# Schematic.net
KiCad netlist of a schematic drawn in Altium Designer
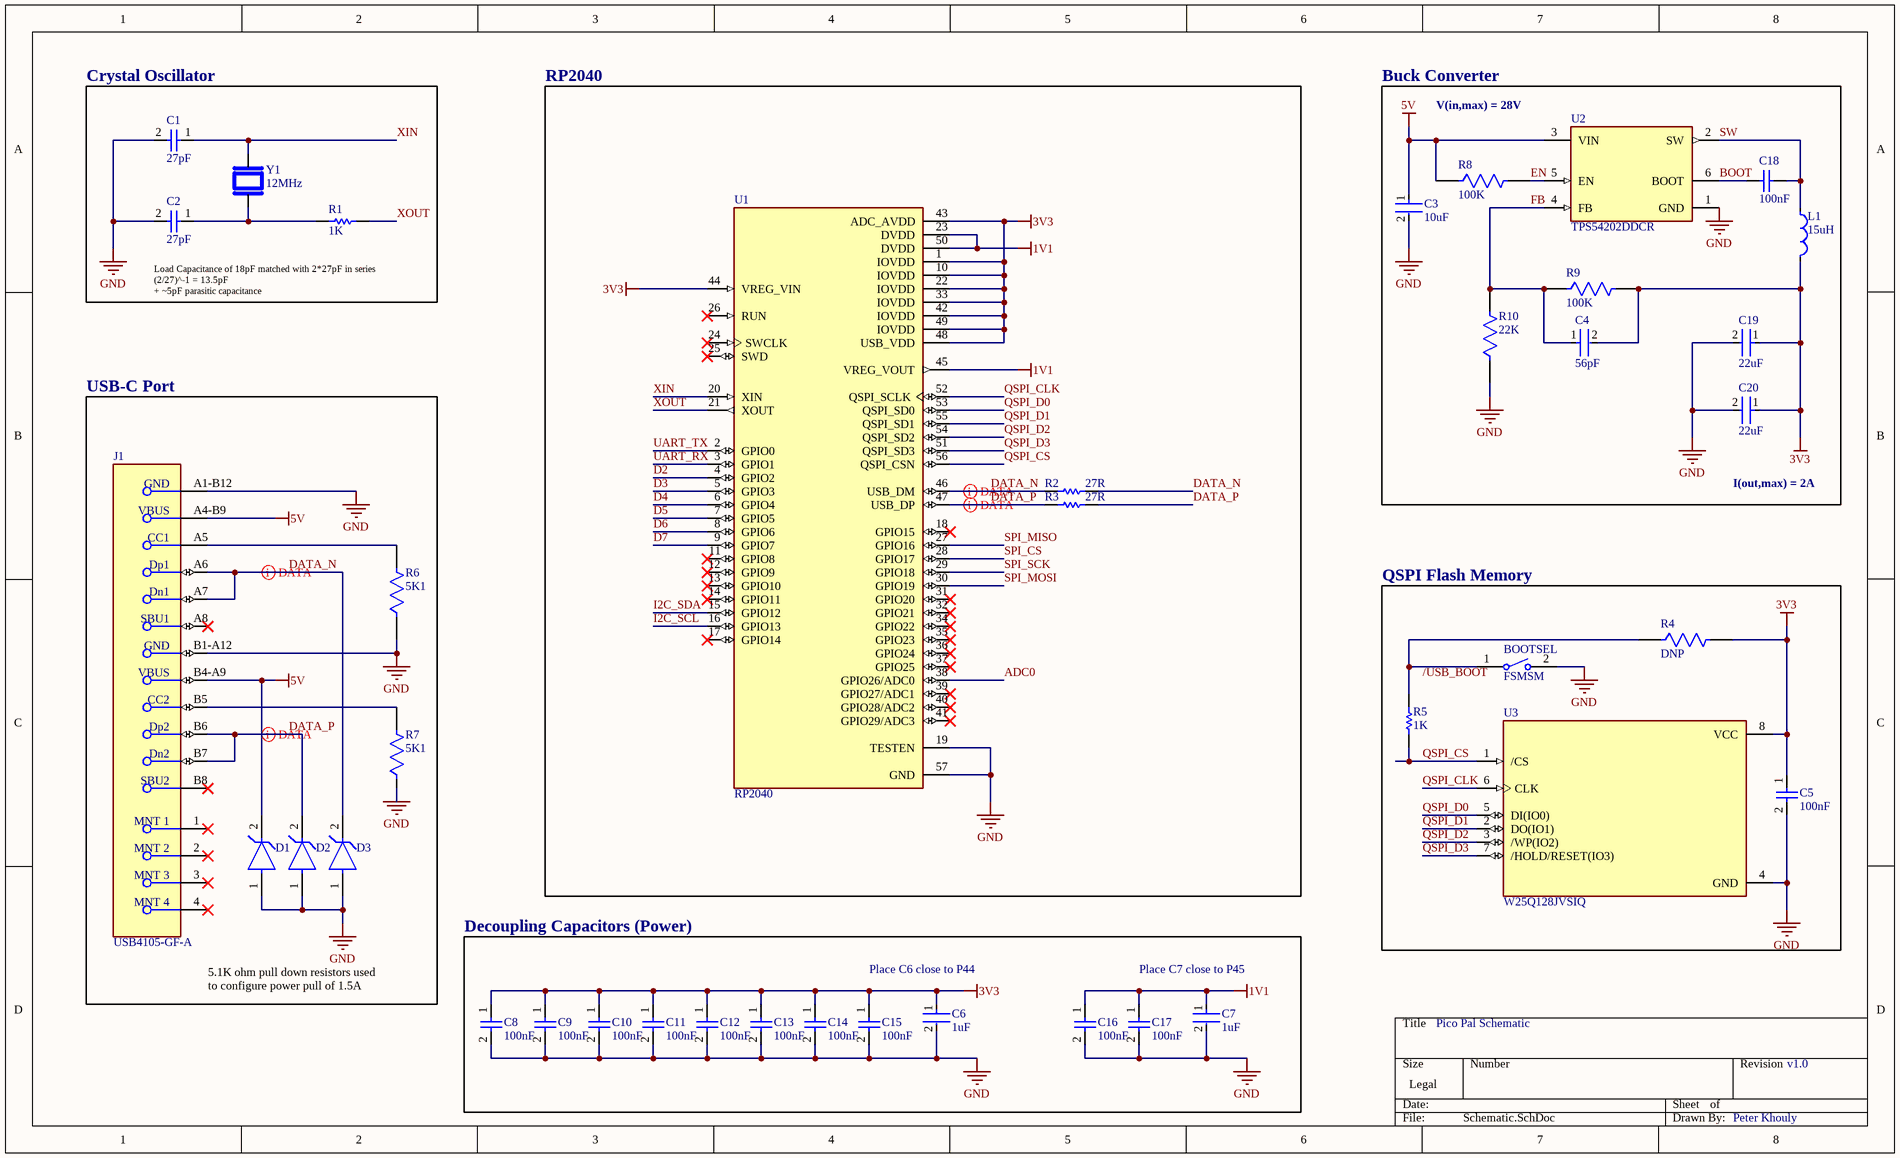
[diagram p0: Schematic.SchDoc]

(export (version "E")
  (design (tool "Eeschema 10.0.6"))
  (components
    (comp (ref "BOOTSEL")
      (value "FSMSM")
      (footprint "TECO-FSMSM-2_V")
      (description "FSMSM Push Button Switch, 50 mA, -35 to 85 degC, 2-Pin SMD, RoHS, Bulk")
      (fields (field (name "MANUFACTURER") "TE Connectivity"))
      (libsource (lib "Altium Content Vault") (part "SW-SPST-2_C"))
    )
    (comp (ref "C1")
      (value "27pF")
      (footprint "CAPC1005X55X25LL05T10")
      (fields (field (name "PART NUMBER") "GRM1555C1H270JA01D") (field (name "MANUFACTURER") "Murata"))
      (libsource (lib "Altium Content Vault") (part "CAP"))
    )
    (comp (ref "C2")
      (value "27pF")
      (footprint "CAPC1005X55X25LL05T10")
      (fields (field (name "PART NUMBER") "GRM1555C1H270JA01D") (field (name "MANUFACTURER") "Murata"))
      (libsource (lib "Altium Content Vault") (part "CAP"))
    )
    (comp (ref "C3")
      (value "10uF")
      (footprint "FP-GRM15-0_2-MFG")
      (description "CAP CER 10UF 6.3V X6S 0402")
      (fields (field (name "TOLERANCE") "20%") (field (name "MANUFACTURER PART NUMBER") "GRM155C80J106ME11D"))
      (libsource (lib "Altium Content Vault") (part "b4654b650e69147ec39a6b967a45e02"))
    )
    (comp (ref "C4")
      (value "56pF")
      (footprint "FP-0402-L_1_0_1-W_0_5_0_1-MFG")
      (description "General Purpose Ceramic Capacitor, 0402, 56pF, 5%, C0G, 30ppm/°C, 50V")
      (fields (field (name "TOLERANCE") "5%") (field (name "VOLTAGE") "50V"))
      (libsource (lib "Altium Content Vault") (part "b4654b650e69147ec39a6b967a45e02"))
    )
    (comp (ref "C5")
      (value "100nF")
      (footprint "CAPC1005X56X25LL10T15")
      (fields
        (field (name "MANUFACTURER") "AVX Interconnect / Elco")
        (field (name "PART NUMBER") "04026D104KAT2A")
      )
      (libsource (lib "Altium Content Vault") (part "CAP"))
    )
    (comp (ref "C6")
      (value "1uF")
      (footprint "FP-GRM15-0_1-MFG")
      (description "CAP CER 1UF 10V X5R 0402")
      (fields
        (field (name "OCTOPART") "https://octopart.com/grm155r61a105ke15d-murata-197442")
        (field (name "MANUFACTURER PART NUMBER") "GRM155R61A105KE15D")
      )
      (libsource (lib "Altium Content Vault") (part "02cd4be3c70576c341d710602a673aa"))
    )
    (comp (ref "C7")
      (value "1uF")
      (footprint "FP-GRM15-0_1-MFG")
      (description "CAP CER 1UF 10V X5R 0402")
      (fields
        (field (name "OCTOPART") "https://octopart.com/grm155r61a105ke15d-murata-197442")
        (field (name "MANUFACTURER PART NUMBER") "GRM155R61A105KE15D")
      )
      (libsource (lib "Altium Content Vault") (part "02cd4be3c70576c341d710602a673aa"))
    )
    (comp (ref "C8")
      (value "100nF")
      (footprint "CAPC1005X56X25LL10T15")
      (fields
        (field (name "MANUFACTURER") "AVX Interconnect / Elco")
        (field (name "PART NUMBER") "04026D104KAT2A")
      )
      (libsource (lib "Altium Content Vault") (part "CAP"))
    )
    (comp (ref "C9")
      (value "100nF")
      (footprint "CAPC1005X56X25LL10T15")
      (fields
        (field (name "MANUFACTURER") "AVX Interconnect / Elco")
        (field (name "PART NUMBER") "04026D104KAT2A")
      )
      (libsource (lib "Altium Content Vault") (part "CAP"))
    )
    (comp (ref "C10")
      (value "100nF")
      (footprint "CAPC1005X56X25LL10T15")
      (fields
        (field (name "MANUFACTURER") "AVX Interconnect / Elco")
        (field (name "PART NUMBER") "04026D104KAT2A")
      )
      (libsource (lib "Altium Content Vault") (part "CAP"))
    )
    (comp (ref "C11")
      (value "100nF")
      (footprint "CAPC1005X56X25LL10T15")
      (fields
        (field (name "MANUFACTURER") "AVX Interconnect / Elco")
        (field (name "PART NUMBER") "04026D104KAT2A")
      )
      (libsource (lib "Altium Content Vault") (part "CAP"))
    )
    (comp (ref "C12")
      (value "100nF")
      (footprint "CAPC1005X56X25LL10T15")
      (fields
        (field (name "MANUFACTURER") "AVX Interconnect / Elco")
        (field (name "PART NUMBER") "04026D104KAT2A")
      )
      (libsource (lib "Altium Content Vault") (part "CAP"))
    )
    (comp (ref "C13")
      (value "100nF")
      (footprint "CAPC1005X56X25LL10T15")
      (fields
        (field (name "MANUFACTURER") "AVX Interconnect / Elco")
        (field (name "PART NUMBER") "04026D104KAT2A")
      )
      (libsource (lib "Altium Content Vault") (part "CAP"))
    )
    (comp (ref "C14")
      (value "100nF")
      (footprint "CAPC1005X56X25LL10T15")
      (fields
        (field (name "MANUFACTURER") "AVX Interconnect / Elco")
        (field (name "PART NUMBER") "04026D104KAT2A")
      )
      (libsource (lib "Altium Content Vault") (part "CAP"))
    )
    (comp (ref "C15")
      (value "100nF")
      (footprint "CAPC1005X56X25LL10T15")
      (fields
        (field (name "MANUFACTURER") "AVX Interconnect / Elco")
        (field (name "PART NUMBER") "04026D104KAT2A")
      )
      (libsource (lib "Altium Content Vault") (part "CAP"))
    )
    (comp (ref "C16")
      (value "100nF")
      (footprint "CAPC1005X56X25LL10T15")
      (fields
        (field (name "MANUFACTURER") "AVX Interconnect / Elco")
        (field (name "PART NUMBER") "04026D104KAT2A")
      )
      (libsource (lib "Altium Content Vault") (part "CAP"))
    )
    (comp (ref "C17")
      (value "100nF")
      (footprint "CAPC1005X56X25LL10T15")
      (fields
        (field (name "MANUFACTURER") "AVX Interconnect / Elco")
        (field (name "PART NUMBER") "04026D104KAT2A")
      )
      (libsource (lib "Altium Content Vault") (part "CAP"))
    )
    (comp (ref "C18")
      (value "100nF")
      (footprint "CAPC1005X56X25LL10T15")
      (fields
        (field (name "MANUFACTURER") "AVX Interconnect / Elco")
        (field (name "PART NUMBER") "04026D104KAT2A")
      )
      (libsource (lib "") (part "CAP_1"))
    )
    (comp (ref "C19")
      (value "22uF")
      (footprint "FP-CL746-IPC_C")
      (description "Cap Ceramic 22uF 6.3V X5R ±20% SMD 0402 +85°C Paper T/R")
      (fields (field (name "TOLERANCE") "20%"))
      (libsource (lib "Altium Content Vault") (part "b4654b650e69147ec39a6b967a45e02"))
    )
    (comp (ref "C20")
      (value "22uF")
      (footprint "FP-CL746-IPC_C")
      (description "Cap Ceramic 22uF 6.3V X5R ±20% SMD 0402 +85°C Paper T/R")
      (fields (field (name "TOLERANCE") "20%"))
      (libsource (lib "Altium Content Vault") (part "b4654b650e69147ec39a6b967a45e02"))
    )
    (comp (ref "D1")
      (value "~")
      (footprint "FP-SLP1006P2-MFG")
      (description "TVS DIODE 33VWM 60VC SLP1006P2")
      (libsource (lib "Altium Content Vault") (part "3fba79ac723ca0a4e69928609483429"))
    )
    (comp (ref "D2")
      (value "~")
      (footprint "FP-SLP1006P2-MFG")
      (description "TVS DIODE 33VWM 60VC SLP1006P2")
      (libsource (lib "Altium Content Vault") (part "3fba79ac723ca0a4e69928609483429"))
    )
    (comp (ref "D3")
      (value "~")
      (footprint "FP-SLP1006P2-MFG")
      (description "TVS DIODE 33VWM 60VC SLP1006P2")
      (libsource (lib "Altium Content Vault") (part "3fba79ac723ca0a4e69928609483429"))
    )
    (comp (ref "J1")
      (value "USB4105-GF-A")
      (footprint "FP-USB4105-GF-A-MFG")
      (description "CONN RCPT USB2.0 TYPEC 5A")
      (fields
        (field (name "MANUFACTURER") "GCT")
        (field (name "OCTOPART") "https://octopart.com/usb4105-gf-a-gct-106627878")
      )
      (libsource (lib "Altium Content Vault") (part "e7c17a616881a82b79941196b4bec10"))
    )
    (comp (ref "L1")
      (value "15uH")
      (footprint "FP-MLZ2012-1_25-IPC_B")
      (description "Shielded Multilayer Inductor 15uH ±20% 350mA 611mΩ SMD 0805")
      (fields (field (name "TOLERANCE") "20%"))
      (libsource (lib "Altium Content Vault") (part "725321dda6339637d4d059423bc1c3c"))
    )
    (comp (ref "R1")
      (value "1K")
      (footprint "RESC1005X40X25NL05T05")
      (description "Chip Resistor, 1 KOhm, +/- 1%, 100 mW, -55 to 155 degC, 0402 (1005 Metric), RoHS, Tape and Reel")
      (fields (field (name "PARTNUMBER") "ERJ-2RKF1001X") (field (name "MANUFACTURER") "Basic Passives"))
      (libsource (lib "Altium Content Vault") (part "RES-2"))
    )
    (comp (ref "R2")
      (value "27R")
      (footprint "RESC1005X40X25LL05T05")
      (fields (field (name "MANUFACTURER") "Panasonic") (field (name "PART NUMBER") "ERJ-2GEJ270X"))
      (libsource (lib "Altium Content Vault") (part "RES"))
    )
    (comp (ref "R3")
      (value "27R")
      (footprint "RESC1005X40X25LL05T05")
      (fields (field (name "MANUFACTURER") "Panasonic") (field (name "PART NUMBER") "ERJ-2GEJ270X"))
      (libsource (lib "Altium Content Vault") (part "RES"))
    )
    (comp (ref "R4")
      (value "DNP")
      (footprint "FP-CRCW1206-e3-IPC_C")
      (description "RES Thick Film, 10kΩ, 1%, 0.25W, 100ppm/°C, 1206")
      (fields (field (name "TOLERANCE") "1%"))
      (libsource (lib "Altium Content Vault") (part "1029c3af85768c4190bb7ad29bc67b5"))
    )
    (comp (ref "R5")
      (value "1K")
      (footprint "RESC1005X40X25NL05T05")
      (description "Chip Resistor, 1 KOhm, +/- 1%, 100 mW, -55 to 155 degC, 0402 (1005 Metric), RoHS, Tape and Reel")
      (fields (field (name "PARTNUMBER") "ERJ-2RKF1001X") (field (name "MANUFACTURER") "Basic Passives"))
      (libsource (lib "Altium Content Vault") (part "RES-2"))
    )
    (comp (ref "R6")
      (value "5K1")
      (footprint "FP-ERJ2RK-IPC_A")
      (description "RES SMD 5.1K OHM 1% 1/10W 0402")
      (fields (field (name "TOLERANCE") "1%"))
      (libsource (lib "Altium Content Vault") (part "1029c3af85768c4190bb7ad29bc67b5"))
    )
    (comp (ref "R7")
      (value "5K1")
      (footprint "FP-ERJ2RK-IPC_A")
      (description "RES SMD 5.1K OHM 1% 1/10W 0402")
      (fields (field (name "TOLERANCE") "1%"))
      (libsource (lib "Altium Content Vault") (part "1029c3af85768c4190bb7ad29bc67b5"))
    )
    (comp (ref "R8")
      (value "100K")
      (footprint "FP-ERJ2RK-IPC_C")
      (description "RES SMD 100K OHM 1% 1/10W 0402")
      (fields (field (name "TOLERANCE") "1%"))
      (libsource (lib "Altium Content Vault") (part "1029c3af85768c4190bb7ad29bc67b5"))
    )
    (comp (ref "R9")
      (value "100K")
      (footprint "FP-ERJ2RK-IPC_C")
      (description "RES SMD 100K OHM 1% 1/10W 0402")
      (fields (field (name "TOLERANCE") "1%"))
      (libsource (lib "Altium Content Vault") (part "1029c3af85768c4190bb7ad29bc67b5"))
    )
    (comp (ref "R10")
      (value "22K")
      (footprint "FP-ERJ2RK-MFG")
      (description "RES SMD 22K OHM 1% 1/10W 0402")
      (fields (field (name "TOLERANCE") "1%"))
      (libsource (lib "Altium Content Vault") (part "1029c3af85768c4190bb7ad29bc67b5"))
    )
    (comp (ref "U1")
      (value "RP2040")
      (footprint "QFN40P700X700X90-57N")
      (description "RP2040 chip for Raspberry Pi Pico - ARMÂ® CortexÂ®-M0+ MCU 32-Bit")
      (fields (field (name "MF") "Raspberry Pi"))
      (libsource (lib "RP2040") (part "RP2040"))
    )
    (comp (ref "U2")
      (value "TPS54202DDCR")
      (footprint "FP-DDC0006A-IPC_B")
      (description "IC REG BUCK ADJ 2A TSOT23-6")
      (libsource (lib "Altium Content Vault") (part "35c2d3f1afc239a386b2ba50eead654"))
    )
    (comp (ref "U3")
      (value "W25Q128JVSIQ")
      (footprint "SOIC127P790X216-8N")
      (description "FLASH - NOR Memory IC 128Mb (16M x 8) SPI - Quad I/O, QPI, DTR 133 MHz 8-SOIC")
      (fields (field (name "MF") "Winbond Electronics"))
      (libsource (lib "W25Q128JVSIQ") (part "W25Q128JVSIQ"))
    )
    (comp (ref "Y1")
      (value "12MHz")
      (footprint "XTAL_ABLS-12.000MHZ-B4-T")
      (description "HC/49US (AT49) SMD LOW PROFILE CRYSTAL")
      (fields (field (name "MF") "Abracon LLC") (field (name "MP") "ABLS-12.000MHZ-B4-T"))
      (libsource (lib "ABLS-12.000MHZ-B4-T") (part "ABLS-12.000MHZ-B4-T"))
    )
  )
  (nets
    (net (code "1") (name "/ADC0") (class "Default")
      (node (ref "U1") (pin "38") (pinfunction "GPIO26/ADC0_38") (pintype "bidirectional"))
    )
    (net (code "2") (name "/BOOT") (class "Default")
      (node (ref "C18") (pin "2") (pinfunction "2_2") (pintype "passive"))
      (node (ref "U2") (pin "6") (pinfunction "BOOT_6") (pintype "passive"))
    )
    (net (code "3") (name "/D2") (class "Default")
      (node (ref "U1") (pin "4") (pinfunction "GPIO2_4") (pintype "bidirectional"))
    )
    (net (code "4") (name "/D3") (class "Default")
      (node (ref "U1") (pin "5") (pinfunction "GPIO3_5") (pintype "bidirectional"))
    )
    (net (code "5") (name "/D4") (class "Default")
      (node (ref "U1") (pin "6") (pinfunction "GPIO4_6") (pintype "bidirectional"))
    )
    (net (code "6") (name "/D5") (class "Default")
      (node (ref "U1") (pin "7") (pinfunction "GPIO5_7") (pintype "bidirectional"))
    )
    (net (code "7") (name "/D6") (class "Default")
      (node (ref "U1") (pin "8") (pinfunction "GPIO6_8") (pintype "bidirectional"))
    )
    (net (code "8") (name "/D7") (class "Default")
      (node (ref "U1") (pin "9") (pinfunction "GPIO7_9") (pintype "bidirectional"))
    )
    (net (code "9") (name "/DATA_N") (class "Default")
      (node (ref "D3") (pin "2") (pinfunction "C_2") (pintype "passive"))
      (node (ref "J1") (pin "A6") (pinfunction "Dp1_A6") (pintype "bidirectional"))
      (node (ref "J1") (pin "A7") (pinfunction "Dn1_A7") (pintype "bidirectional"))
      (node (ref "R2") (pin "1") (pinfunction "1_1") (pintype "passive"))
      (node (ref "R2") (pin "2") (pinfunction "2_2") (pintype "passive"))
      (node (ref "U1") (pin "46") (pinfunction "USB_DM_46") (pintype "bidirectional"))
    )
    (net (code "10") (name "/DATA_P") (class "Default")
      (node (ref "D2") (pin "2") (pinfunction "C_2") (pintype "passive"))
      (node (ref "J1") (pin "B6") (pinfunction "Dp2_B6") (pintype "bidirectional"))
      (node (ref "J1") (pin "B7") (pinfunction "Dn2_B7") (pintype "bidirectional"))
      (node (ref "R3") (pin "1") (pinfunction "1_1") (pintype "passive"))
      (node (ref "R3") (pin "2") (pinfunction "2_2") (pintype "passive"))
      (node (ref "U1") (pin "47") (pinfunction "USB_DP_47") (pintype "bidirectional"))
    )
    (net (code "11") (name "/EN") (class "Default")
      (node (ref "R8") (pin "2") (pinfunction "2_2") (pintype "passive"))
      (node (ref "U2") (pin "5") (pinfunction "EN_5") (pintype "input"))
    )
    (net (code "12") (name "/FB") (class "Default")
      (node (ref "C4") (pin "1") (pinfunction "1_1") (pintype "passive"))
      (node (ref "R10") (pin "2") (pinfunction "2_2") (pintype "passive"))
      (node (ref "R9") (pin "1") (pinfunction "1_1") (pintype "passive"))
      (node (ref "U2") (pin "4") (pinfunction "FB_4") (pintype "input"))
    )
    (net (code "13") (name "/I2C_SCL") (class "Default")
      (node (ref "U1") (pin "16") (pinfunction "GPIO13_16") (pintype "bidirectional"))
    )
    (net (code "14") (name "/I2C_SDA") (class "Default")
      (node (ref "U1") (pin "15") (pinfunction "GPIO12_15") (pintype "bidirectional"))
    )
    (net (code "15") (name "/QSPI_CLK") (class "Default")
      (node (ref "U1") (pin "52") (pinfunction "QSPI_SCLK_52") (pintype "bidirectional"))
      (node (ref "U3") (pin "6") (pinfunction "CLK_6") (pintype "input"))
    )
    (net (code "16") (name "/QSPI_CS") (class "Default")
      (node (ref "R5") (pin "1") (pinfunction "1_1") (pintype "passive"))
      (node (ref "U1") (pin "56") (pinfunction "QSPI_CSN_56") (pintype "bidirectional"))
      (node (ref "U3") (pin "1") (pinfunction "/CS_1") (pintype "input"))
    )
    (net (code "17") (name "/QSPI_D0") (class "Default")
      (node (ref "U1") (pin "53") (pinfunction "QSPI_SD0_53") (pintype "bidirectional"))
      (node (ref "U3") (pin "5") (pinfunction "DI(IO0)_5") (pintype "bidirectional"))
    )
    (net (code "18") (name "/QSPI_D1") (class "Default")
      (node (ref "U1") (pin "55") (pinfunction "QSPI_SD1_55") (pintype "bidirectional"))
      (node (ref "U3") (pin "2") (pinfunction "DO(IO1)_2") (pintype "bidirectional"))
    )
    (net (code "19") (name "/QSPI_D2") (class "Default")
      (node (ref "U1") (pin "54") (pinfunction "QSPI_SD2_54") (pintype "bidirectional"))
      (node (ref "U3") (pin "3") (pinfunction "/WP(IO2)_3") (pintype "bidirectional"))
    )
    (net (code "20") (name "/QSPI_D3") (class "Default")
      (node (ref "U1") (pin "51") (pinfunction "QSPI_SD3_51") (pintype "bidirectional"))
      (node (ref "U3") (pin "7") (pinfunction "/HOLD/RESET(IO3)_7") (pintype "bidirectional"))
    )
    (net (code "21") (name "/SPI_CS") (class "Default")
      (node (ref "U1") (pin "28") (pinfunction "GPIO17_28") (pintype "bidirectional"))
    )
    (net (code "22") (name "/SPI_MISO") (class "Default")
      (node (ref "U1") (pin "27") (pinfunction "GPIO16_27") (pintype "bidirectional"))
    )
    (net (code "23") (name "/SPI_MOSI") (class "Default")
      (node (ref "U1") (pin "30") (pinfunction "GPIO19_30") (pintype "bidirectional"))
    )
    (net (code "24") (name "/SPI_SCK") (class "Default")
      (node (ref "U1") (pin "29") (pinfunction "GPIO18_29") (pintype "bidirectional"))
    )
    (net (code "25") (name "/SW") (class "Default")
      (node (ref "C18") (pin "1") (pinfunction "1_1") (pintype "passive"))
      (node (ref "L1") (pin "1") (pinfunction "1_1") (pintype "passive"))
      (node (ref "U2") (pin "2") (pinfunction "SW_2") (pintype "output"))
    )
    (net (code "26") (name "/UART_RX") (class "Default")
      (node (ref "U1") (pin "3") (pinfunction "GPIO1_3") (pintype "bidirectional"))
    )
    (net (code "27") (name "/UART_TX") (class "Default")
      (node (ref "U1") (pin "2") (pinfunction "GPIO0_2") (pintype "bidirectional"))
    )
    (net (code "28") (name "/XIN") (class "Default")
      (node (ref "C1") (pin "1") (pinfunction "1_1") (pintype "passive"))
      (node (ref "U1") (pin "20") (pinfunction "XIN_20") (pintype "input"))
      (node (ref "Y1") (pin "2") (pinfunction "2_2") (pintype "passive"))
    )
    (net (code "29") (name "/XOUT") (class "Default")
      (node (ref "R1") (pin "2") (pinfunction "2_2") (pintype "passive"))
      (node (ref "U1") (pin "21") (pinfunction "XOUT_21") (pintype "output"))
    )
    (net (code "31") (name "1V1") (class "Default")
      (node (ref "C16") (pin "1") (pinfunction "1_1") (pintype "passive"))
      (node (ref "C17") (pin "1") (pinfunction "1_1") (pintype "passive"))
      (node (ref "C7") (pin "1") (pinfunction "1_1") (pintype "passive"))
      (node (ref "U1") (pin "23") (pinfunction "DVDD_23") (pintype "power_in"))
      (node (ref "U1") (pin "45") (pinfunction "VREG_VOUT_45") (pintype "output"))
      (node (ref "U1") (pin "50") (pinfunction "DVDD_50") (pintype "power_in"))
    )
    (net (code "32") (name "3V3") (class "Default")
      (node (ref "C10") (pin "1") (pinfunction "1_1") (pintype "passive"))
      (node (ref "C11") (pin "1") (pinfunction "1_1") (pintype "passive"))
      (node (ref "C12") (pin "1") (pinfunction "1_1") (pintype "passive"))
      (node (ref "C13") (pin "1") (pinfunction "1_1") (pintype "passive"))
      (node (ref "C14") (pin "1") (pinfunction "1_1") (pintype "passive"))
      (node (ref "C15") (pin "1") (pinfunction "1_1") (pintype "passive"))
      (node (ref "C19") (pin "1") (pinfunction "1_1") (pintype "passive"))
      (node (ref "C20") (pin "1") (pinfunction "1_1") (pintype "passive"))
      (node (ref "C4") (pin "2") (pinfunction "2_2") (pintype "passive"))
      (node (ref "C5") (pin "1") (pinfunction "1_1") (pintype "passive"))
      (node (ref "C6") (pin "1") (pinfunction "1_1") (pintype "passive"))
      (node (ref "C8") (pin "1") (pinfunction "1_1") (pintype "passive"))
      (node (ref "C9") (pin "1") (pinfunction "1_1") (pintype "passive"))
      (node (ref "L1") (pin "2") (pinfunction "2_2") (pintype "passive"))
      (node (ref "R4") (pin "2") (pinfunction "2_2") (pintype "passive"))
      (node (ref "R9") (pin "2") (pinfunction "2_2") (pintype "passive"))
      (node (ref "U1") (pin "1") (pinfunction "IOVDD_1") (pintype "power_in"))
      (node (ref "U1") (pin "10") (pinfunction "IOVDD_10") (pintype "power_in"))
      (node (ref "U1") (pin "22") (pinfunction "IOVDD_22") (pintype "power_in"))
      (node (ref "U1") (pin "33") (pinfunction "IOVDD_33") (pintype "power_in"))
      (node (ref "U1") (pin "42") (pinfunction "IOVDD_42") (pintype "power_in"))
      (node (ref "U1") (pin "43") (pinfunction "ADC_AVDD_43") (pintype "power_in"))
      (node (ref "U1") (pin "44") (pinfunction "VREG_VIN_44") (pintype "input"))
      (node (ref "U1") (pin "48") (pinfunction "USB_VDD_48") (pintype "power_in"))
      (node (ref "U1") (pin "49") (pinfunction "IOVDD_49") (pintype "power_in"))
      (node (ref "U3") (pin "8") (pinfunction "VCC_8") (pintype "power_in"))
    )
    (net (code "33") (name "5V") (class "Default")
      (node (ref "C3") (pin "1") (pinfunction "1_1") (pintype "passive"))
      (node (ref "D1") (pin "2") (pinfunction "C_2") (pintype "passive"))
      (node (ref "J1") (pin "A4-B9") (pinfunction "VBUS_A4-B9") (pintype "power_in"))
      (node (ref "J1") (pin "B4-A9") (pinfunction "VBUS_B4-A9") (pintype "bidirectional"))
      (node (ref "R8") (pin "1") (pinfunction "1_1") (pintype "passive"))
      (node (ref "U2") (pin "3") (pinfunction "VIN_3") (pintype "power_in"))
    )
    (net (code "34") (name "GND") (class "Default")
      (node (ref "BOOTSEL") (pin "2") (pinfunction "2_2") (pintype "passive"))
      (node (ref "C1") (pin "2") (pinfunction "2_2") (pintype "passive"))
      (node (ref "C10") (pin "2") (pinfunction "2_2") (pintype "passive"))
      (node (ref "C11") (pin "2") (pinfunction "2_2") (pintype "passive"))
      (node (ref "C12") (pin "2") (pinfunction "2_2") (pintype "passive"))
      (node (ref "C13") (pin "2") (pinfunction "2_2") (pintype "passive"))
      (node (ref "C14") (pin "2") (pinfunction "2_2") (pintype "passive"))
      (node (ref "C15") (pin "2") (pinfunction "2_2") (pintype "passive"))
      (node (ref "C16") (pin "2") (pinfunction "2_2") (pintype "passive"))
      (node (ref "C17") (pin "2") (pinfunction "2_2") (pintype "passive"))
      (node (ref "C19") (pin "2") (pinfunction "2_2") (pintype "passive"))
      (node (ref "C2") (pin "2") (pinfunction "2_2") (pintype "passive"))
      (node (ref "C20") (pin "2") (pinfunction "2_2") (pintype "passive"))
      (node (ref "C3") (pin "2") (pinfunction "2_2") (pintype "passive"))
      (node (ref "C5") (pin "2") (pinfunction "2_2") (pintype "passive"))
      (node (ref "C6") (pin "2") (pinfunction "2_2") (pintype "passive"))
      (node (ref "C7") (pin "2") (pinfunction "2_2") (pintype "passive"))
      (node (ref "C8") (pin "2") (pinfunction "2_2") (pintype "passive"))
      (node (ref "C9") (pin "2") (pinfunction "2_2") (pintype "passive"))
      (node (ref "D1") (pin "1") (pinfunction "A_1") (pintype "passive"))
      (node (ref "D2") (pin "1") (pinfunction "A_1") (pintype "passive"))
      (node (ref "D3") (pin "1") (pinfunction "A_1") (pintype "passive"))
      (node (ref "J1") (pin "A1-B12") (pinfunction "GND_A1-B12") (pintype "power_in"))
      (node (ref "J1") (pin "B1-A12") (pinfunction "GND_B1-A12") (pintype "bidirectional"))
      (node (ref "R10") (pin "1") (pinfunction "1_1") (pintype "passive"))
      (node (ref "R6") (pin "1") (pinfunction "1_1") (pintype "passive"))
      (node (ref "R7") (pin "1") (pinfunction "1_1") (pintype "passive"))
      (node (ref "U1") (pin "19") (pinfunction "TESTEN_19") (pintype "passive"))
      (node (ref "U1") (pin "57") (pinfunction "GND_57") (pintype "power_in"))
      (node (ref "U2") (pin "1") (pinfunction "GND_1") (pintype "power_in"))
      (node (ref "U3") (pin "4") (pinfunction "GND_4") (pintype "power_in"))
    )
    (net (code "35") (name "Net-(BOOTSEL-Pad1)") (class "Default")
      (node (ref "BOOTSEL") (pin "1") (pinfunction "1_1") (pintype "passive"))
      (node (ref "R4") (pin "1") (pinfunction "1_1") (pintype "passive"))
      (node (ref "R5") (pin "2") (pinfunction "2_2") (pintype "passive"))
    )
    (net (code "36") (name "Net-(C2-Pad1)") (class "Default")
      (node (ref "C2") (pin "1") (pinfunction "1_1") (pintype "passive"))
      (node (ref "R1") (pin "1") (pinfunction "1_1") (pintype "passive"))
      (node (ref "Y1") (pin "1") (pinfunction "1_1") (pintype "passive"))
    )
    (net (code "37") (name "Net-(J1-CC1)") (class "Default")
      (node (ref "J1") (pin "A5") (pinfunction "CC1_A5") (pintype "power_in"))
      (node (ref "R6") (pin "2") (pinfunction "2_2") (pintype "passive"))
    )
    (net (code "38") (name "Net-(J1-CC2)") (class "Default")
      (node (ref "J1") (pin "B5") (pinfunction "CC2_B5") (pintype "bidirectional"))
      (node (ref "R7") (pin "2") (pinfunction "2_2") (pintype "passive"))
    )
    (net (code "39") (name "unconnected-(J1-MNT_1-Pad1)") (class "Default")
      (node (ref "J1") (pin "1") (pinfunction "MNT_1_1") (pintype "power_in+no_connect"))
    )
    (net (code "40") (name "unconnected-(J1-MNT_2-Pad2)") (class "Default")
      (node (ref "J1") (pin "2") (pinfunction "MNT_2_2") (pintype "power_in+no_connect"))
    )
    (net (code "41") (name "unconnected-(J1-MNT_3-Pad3)") (class "Default")
      (node (ref "J1") (pin "3") (pinfunction "MNT_3_3") (pintype "power_in+no_connect"))
    )
    (net (code "42") (name "unconnected-(J1-MNT_4-Pad4)") (class "Default")
      (node (ref "J1") (pin "4") (pinfunction "MNT_4_4") (pintype "power_in+no_connect"))
    )
    (net (code "43") (name "unconnected-(J1-SBU1-PadA8)") (class "Default")
      (node (ref "J1") (pin "A8") (pinfunction "SBU1_A8") (pintype "bidirectional+no_connect"))
    )
    (net (code "44") (name "unconnected-(J1-SBU2-PadB8)") (class "Default")
      (node (ref "J1") (pin "B8") (pinfunction "SBU2_B8") (pintype "power_in+no_connect"))
    )
    (net (code "45") (name "unconnected-(U1-GPIO8-Pad11)") (class "Default")
      (node (ref "U1") (pin "11") (pinfunction "GPIO8_11") (pintype "bidirectional+no_connect"))
    )
    (net (code "46") (name "unconnected-(U1-GPIO9-Pad12)") (class "Default")
      (node (ref "U1") (pin "12") (pinfunction "GPIO9_12") (pintype "bidirectional+no_connect"))
    )
    (net (code "47") (name "unconnected-(U1-GPIO10-Pad13)") (class "Default")
      (node (ref "U1") (pin "13") (pinfunction "GPIO10_13") (pintype "bidirectional+no_connect"))
    )
    (net (code "48") (name "unconnected-(U1-GPIO11-Pad14)") (class "Default")
      (node (ref "U1") (pin "14") (pinfunction "GPIO11_14") (pintype "bidirectional+no_connect"))
    )
    (net (code "49") (name "unconnected-(U1-GPIO14-Pad17)") (class "Default")
      (node (ref "U1") (pin "17") (pinfunction "GPIO14_17") (pintype "bidirectional+no_connect"))
    )
    (net (code "50") (name "unconnected-(U1-GPIO15-Pad18)") (class "Default")
      (node (ref "U1") (pin "18") (pinfunction "GPIO15_18") (pintype "bidirectional+no_connect"))
    )
    (net (code "51") (name "unconnected-(U1-GPIO20-Pad31)") (class "Default")
      (node (ref "U1") (pin "31") (pinfunction "GPIO20_31") (pintype "bidirectional+no_connect"))
    )
    (net (code "52") (name "unconnected-(U1-GPIO21-Pad32)") (class "Default")
      (node (ref "U1") (pin "32") (pinfunction "GPIO21_32") (pintype "bidirectional+no_connect"))
    )
    (net (code "53") (name "unconnected-(U1-GPIO22-Pad34)") (class "Default")
      (node (ref "U1") (pin "34") (pinfunction "GPIO22_34") (pintype "bidirectional+no_connect"))
    )
    (net (code "54") (name "unconnected-(U1-GPIO23-Pad35)") (class "Default")
      (node (ref "U1") (pin "35") (pinfunction "GPIO23_35") (pintype "bidirectional+no_connect"))
    )
    (net (code "55") (name "unconnected-(U1-GPIO24-Pad36)") (class "Default")
      (node (ref "U1") (pin "36") (pinfunction "GPIO24_36") (pintype "bidirectional+no_connect"))
    )
    (net (code "56") (name "unconnected-(U1-GPIO25-Pad37)") (class "Default")
      (node (ref "U1") (pin "37") (pinfunction "GPIO25_37") (pintype "bidirectional+no_connect"))
    )
    (net (code "57") (name "unconnected-(U1-GPIO27{slash}ADC1-Pad39)") (class "Default")
      (node (ref "U1") (pin "39") (pinfunction "GPIO27/ADC1_39") (pintype "bidirectional+no_connect"))
    )
    (net (code "58") (name "unconnected-(U1-GPIO28{slash}ADC2-Pad40)") (class "Default")
      (node (ref "U1") (pin "40") (pinfunction "GPIO28/ADC2_40") (pintype "bidirectional+no_connect"))
    )
    (net (code "59") (name "unconnected-(U1-GPIO29{slash}ADC3-Pad41)") (class "Default")
      (node (ref "U1") (pin "41") (pinfunction "GPIO29/ADC3_41") (pintype "bidirectional+no_connect"))
    )
    (net (code "60") (name "unconnected-(U1-RUN-Pad26)") (class "Default")
      (node (ref "U1") (pin "26") (pinfunction "RUN_26") (pintype "input+no_connect"))
    )
    (net (code "61") (name "unconnected-(U1-SWCLK-Pad24)") (class "Default")
      (node (ref "U1") (pin "24") (pinfunction "SWCLK_24") (pintype "input+no_connect"))
    )
    (net (code "62") (name "unconnected-(U1-SWD-Pad25)") (class "Default")
      (node (ref "U1") (pin "25") (pinfunction "SWD_25") (pintype "bidirectional+no_connect"))
    )
  )
)
